# Sheet2-power.net
KiCad netlist of a schematic drawn in Altium Designer
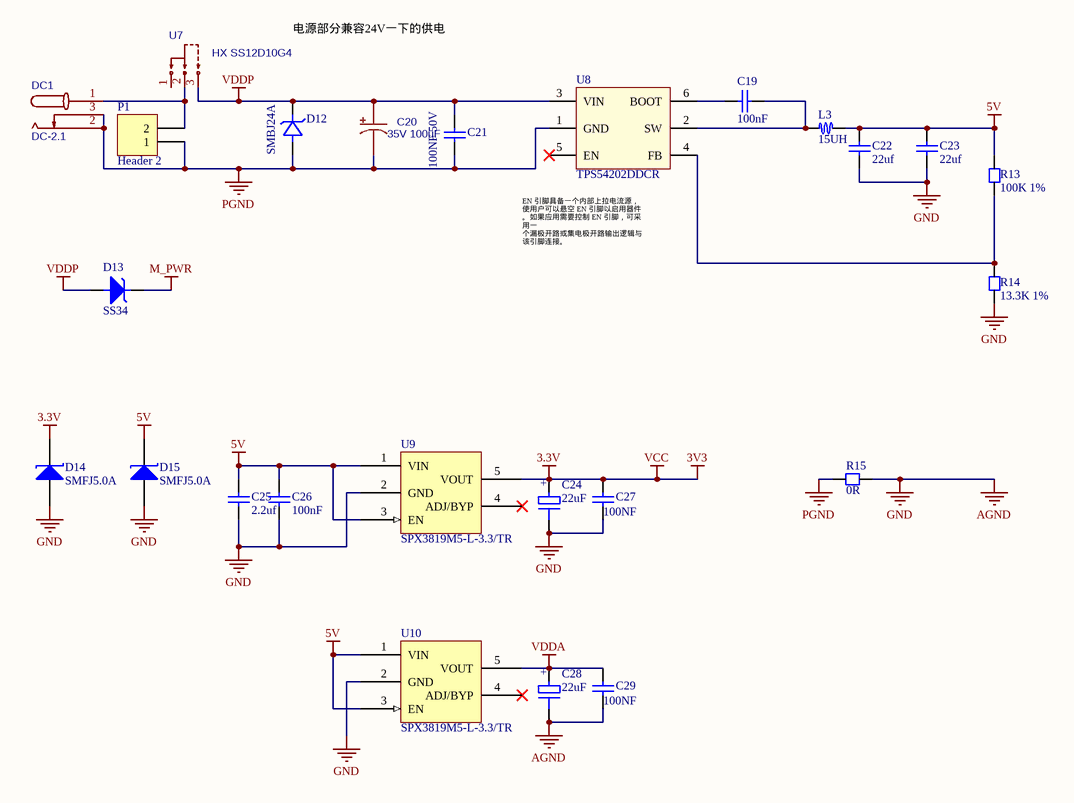
[diagram p0: Sheet2-power.SchDoc]

(export (version "E")
  (design (tool "Eeschema 10.0.6"))
  (components
    (comp (ref "C19")
      (value "100nF")
      (footprint "CC1608-0603")
      (description "0603封装的电容")
      (fields (field (name "PUBLISHER") "Altium Limited"))
      (libsource (lib "base") (part "Cap Chip 0603"))
    )
    (comp (ref "C20")
      (value "35V 100uF")
      (footprint "CAP-SMD_D6.3")
      (description "铝点解电容")
      (fields
        (field (name "BOM_SUPPLIER PART") "C413527")
        (field (name "BOM_MANUFACTURER PART") "EEEFP1C681AP")
        (field (name "CONTRIBUTOR") "LCSC")
      )
      (libsource (lib "base") (part "Cap ECAP SMD"))
    )
    (comp (ref "C21")
      (value "100NF 50V")
      (footprint "CC1608-0603")
      (description "0603封装的电容")
      (fields (field (name "PUBLISHER") "Altium Limited"))
      (libsource (lib "base") (part "Cap Chip 0603"))
    )
    (comp (ref "C22")
      (value "22uf")
      (footprint "CC1608-0603")
      (description "0603封装的电容")
      (fields (field (name "PUBLISHER") "Altium Limited"))
      (libsource (lib "base") (part "Cap Chip 0603"))
    )
    (comp (ref "C23")
      (value "22uf")
      (footprint "CC1608-0603")
      (description "0603封装的电容")
      (fields (field (name "PUBLISHER") "Altium Limited"))
      (libsource (lib "base") (part "Cap Chip 0603"))
    )
    (comp (ref "C24")
      (value "22uF")
      (footprint "TAN-A-1206")
      (description "钽电容")
      (libsource (lib "base") (part "CAP TAN-A-1206"))
    )
    (comp (ref "C25")
      (value "2.2uf")
      (footprint "CC1608-0603")
      (description "0603封装的电容")
      (fields (field (name "PUBLISHER") "Altium Limited"))
      (libsource (lib "base") (part "Cap Chip 0603"))
    )
    (comp (ref "C26")
      (value "100nF")
      (footprint "CC1608-0603")
      (description "0603封装的电容")
      (fields (field (name "PUBLISHER") "Altium Limited"))
      (libsource (lib "base") (part "Cap Chip 0603"))
    )
    (comp (ref "C27")
      (value "100NF")
      (footprint "CC1608-0603")
      (description "贴片电容")
      (libsource (lib "tianxiaohua_Schlib") (part "Chip capacitor"))
    )
    (comp (ref "C28")
      (value "22uF")
      (footprint "TAN-A-1206")
      (description "钽电容")
      (libsource (lib "base") (part "CAP TAN-A-1206"))
    )
    (comp (ref "C29")
      (value "100NF")
      (footprint "CC1608-0603")
      (description "贴片电容")
      (libsource (lib "tianxiaohua_Schlib") (part "Chip capacitor"))
    )
    (comp (ref "D12")
      (value "SMBJ24A")
      (footprint "DO-214 AA")
      (description "TVS稳压二极管")
      (libsource (lib "transistor") (part "SMBJ18A"))
    )
    (comp (ref "D13")
      (value "SS34")
      (footprint "DO-214 AA")
      (description "肖特基二极管")
      (libsource (lib "transistor") (part "SS34"))
    )
    (comp (ref "D14")
      (value "SMFJ5.0A")
      (footprint "SOD-123")
      (description "5V单向贴片TVS瞬变抑制二极管")
      (libsource (lib "transistor") (part "SMFJ5.0A"))
    )
    (comp (ref "D15")
      (value "SMFJ5.0A")
      (footprint "SOD-123")
      (description "5V单向贴片TVS瞬变抑制二极管")
      (libsource (lib "transistor") (part "SMFJ5.0A"))
    )
    (comp (ref "DC1")
      (value "DC-2.1")
      (footprint "DC-IN-SMD_DC-050-25A")
      (description "DC贴片插座")
      (fields
        (field (name "BOM_SUPPLIER PART") "C707275")
        (field (name "BOM_MANUFACTURER PART") "DC-050-25A")
        (field (name "CONTRIBUTOR") "LCSC")
      )
      (libsource (lib "Connectors") (part "DC-050"))
    )
    (comp (ref "L3")
      (value "15UH")
      (footprint "Inductor-0630")
      (description "贴片电感 0630封装")
      (libsource (lib "base") (part "Inductor-0630"))
    )
    (comp (ref "P1")
      (value "Header 2")
      (footprint "HX2.54-2")
      (description "Header, 2-Pin")
      (fields (field (name "PUBLISHER") "Altium Limited"))
      (libsource (lib "Connectors") (part "Header 2"))
    )
    (comp (ref "R13")
      (value "100K 1%")
      (footprint "CR1608-0603")
      (description "0603封装电阻")
      (fields (field (name "PUBLISHER") "Altium Limited"))
      (libsource (lib "") (part "Resistor Chip 0603_1"))
    )
    (comp (ref "R14")
      (value "13.3K 1%")
      (footprint "CR1608-0603")
      (description "0603封装电阻")
      (fields (field (name "PUBLISHER") "Altium Limited"))
      (libsource (lib "") (part "Resistor Chip 0603_1"))
    )
    (comp (ref "R15")
      (value "0R")
      (footprint "CR1608-0603")
      (description "0603封装电阻")
      (fields (field (name "PUBLISHER") "Altium Limited"))
      (libsource (lib "base") (part "Resistor Chip 0603"))
    )
    (comp (ref "U7")
      (value "HX SS12D10G4")
      (footprint "SS12D10-G4")
      (fields (field (name "BOM_SUPPLIER PART") "C5149841") (field (name "CONTRIBUTOR") "lcsc"))
      (libsource (lib "Connectors") (part "SS12D10G4"))
    )
    (comp (ref "U8")
      (value "TPS54202DDCR")
      (footprint "SOT23-6")
      (description "同步降压转换器芯片 500Khz 4.2~28V输入，2A输出")
      (libsource (lib "power-chip") (part "TPS54202DDCR"))
    )
    (comp (ref "U9")
      (value "SPX3819M5-L-3.3/TR")
      (footprint "SOT23-5")
      (description "LDO 3.3V , SOT-23-5 500ma")
      (libsource (lib "power-chip") (part "SPX3819M5-L-3.3/TR"))
    )
    (comp (ref "U10")
      (value "SPX3819M5-L-3.3/TR")
      (footprint "SOT23-5")
      (description "LDO 3.3V , SOT-23-5 500ma")
      (libsource (lib "power-chip") (part "SPX3819M5-L-3.3/TR"))
    )
  )
  (nets
    (net (code "1") (name "3.3V") (class "Default")
      (node (ref "C24") (pin "1") (pinfunction "+_1") (pintype "passive"))
      (node (ref "C27") (pin "1") (pinfunction "1_1") (pintype "passive"))
      (node (ref "D14") (pin "1") (pinfunction "1_1") (pintype "passive"))
      (node (ref "U9") (pin "5") (pinfunction "VOUT_5") (pintype "passive"))
    )
    (net (code "2") (name "5V") (class "Default")
      (node (ref "C22") (pin "2") (pinfunction "2_2") (pintype "passive"))
      (node (ref "C23") (pin "2") (pinfunction "2_2") (pintype "passive"))
      (node (ref "C25") (pin "2") (pinfunction "2_2") (pintype "passive"))
      (node (ref "C26") (pin "2") (pinfunction "2_2") (pintype "passive"))
      (node (ref "D15") (pin "1") (pinfunction "1_1") (pintype "passive"))
      (node (ref "L3") (pin "2") (pinfunction "2_2") (pintype "passive"))
      (node (ref "R13") (pin "2") (pinfunction "2_2") (pintype "passive"))
      (node (ref "U10") (pin "1") (pinfunction "VIN_1") (pintype "power_in"))
      (node (ref "U10") (pin "3") (pinfunction "EN_3") (pintype "input"))
      (node (ref "U9") (pin "1") (pinfunction "VIN_1") (pintype "power_in"))
      (node (ref "U9") (pin "3") (pinfunction "EN_3") (pintype "input"))
    )
    (net (code "3") (name "AGND") (class "Default")
      (node (ref "C22") (pin "1") (pinfunction "1_1") (pintype "passive"))
      (node (ref "C23") (pin "1") (pinfunction "1_1") (pintype "passive"))
      (node (ref "C24") (pin "2") (pinfunction "-_2") (pintype "passive"))
      (node (ref "C25") (pin "1") (pinfunction "1_1") (pintype "passive"))
      (node (ref "C26") (pin "1") (pinfunction "1_1") (pintype "passive"))
      (node (ref "C27") (pin "2") (pinfunction "2_2") (pintype "passive"))
      (node (ref "C28") (pin "2") (pinfunction "-_2") (pintype "passive"))
      (node (ref "C29") (pin "2") (pinfunction "2_2") (pintype "passive"))
      (node (ref "D14") (pin "2") (pinfunction "2_2") (pintype "passive"))
      (node (ref "D15") (pin "2") (pinfunction "2_2") (pintype "passive"))
      (node (ref "R14") (pin "1") (pinfunction "1_1") (pintype "passive"))
      (node (ref "R15") (pin "1") (pinfunction "1_1") (pintype "passive"))
      (node (ref "U10") (pin "2") (pinfunction "GND_2") (pintype "power_in"))
      (node (ref "U9") (pin "2") (pinfunction "GND_2") (pintype "power_in"))
    )
    (net (code "4") (name "M_PWR") (class "Default")
      (node (ref "D13") (pin "1") (pinfunction "K_1") (pintype "passive"))
    )
    (net (code "5") (name "Net-(DC1-Pad1)") (class "Default")
      (node (ref "DC1") (pin "1") (pinfunction "1_1") (pintype "passive"))
      (node (ref "P1") (pin "2") (pinfunction "2_2") (pintype "passive"))
      (node (ref "U7") (pin "2") (pinfunction "2_2") (pintype "passive"))
    )
    (net (code "6") (name "Net-(U8-BOOT)") (class "Default")
      (node (ref "C19") (pin "1") (pinfunction "1_1") (pintype "passive"))
      (node (ref "U8") (pin "6") (pinfunction "BOOT_6") (pintype "passive"))
    )
    (net (code "7") (name "Net-(U8-FB)") (class "Default")
      (node (ref "R13") (pin "1") (pinfunction "1_1") (pintype "passive"))
      (node (ref "R14") (pin "2") (pinfunction "2_2") (pintype "passive"))
      (node (ref "U8") (pin "4") (pinfunction "FB_4") (pintype "passive"))
    )
    (net (code "8") (name "Net-(U8-SW)") (class "Default")
      (node (ref "C19") (pin "2") (pinfunction "2_2") (pintype "passive"))
      (node (ref "L3") (pin "1") (pinfunction "1_1") (pintype "passive"))
      (node (ref "U8") (pin "2") (pinfunction "SW_2") (pintype "passive"))
    )
    (net (code "9") (name "PGND") (class "Default")
      (node (ref "C20") (pin "2") (pinfunction "2_2") (pintype "passive"))
      (node (ref "C21") (pin "1") (pinfunction "1_1") (pintype "passive"))
      (node (ref "D12") (pin "2") (pinfunction "A_2") (pintype "passive"))
      (node (ref "DC1") (pin "2") (pinfunction "2_2") (pintype "passive"))
      (node (ref "DC1") (pin "3") (pinfunction "3_3") (pintype "passive"))
      (node (ref "P1") (pin "1") (pinfunction "1_1") (pintype "passive"))
      (node (ref "R15") (pin "2") (pinfunction "2_2") (pintype "passive"))
      (node (ref "U8") (pin "1") (pinfunction "GND_1") (pintype "passive"))
    )
    (net (code "10") (name "VDDA") (class "Default")
      (node (ref "C28") (pin "1") (pinfunction "+_1") (pintype "passive"))
      (node (ref "C29") (pin "1") (pinfunction "1_1") (pintype "passive"))
      (node (ref "U10") (pin "5") (pinfunction "VOUT_5") (pintype "passive"))
    )
    (net (code "11") (name "VDDP") (class "Default")
      (node (ref "C20") (pin "1") (pinfunction "1_1") (pintype "passive"))
      (node (ref "C21") (pin "2") (pinfunction "2_2") (pintype "passive"))
      (node (ref "D12") (pin "1") (pinfunction "K_1") (pintype "passive"))
      (node (ref "D13") (pin "2") (pinfunction "A_2") (pintype "passive"))
      (node (ref "U7") (pin "3") (pinfunction "3_3") (pintype "passive"))
      (node (ref "U8") (pin "3") (pinfunction "VIN_3") (pintype "passive"))
    )
    (net (code "12") (name "unconnected-(U7-Pad1)") (class "Default")
      (node (ref "U7") (pin "1") (pinfunction "1_1") (pintype "passive"))
    )
    (net (code "13") (name "unconnected-(U8-EN-Pad5)") (class "Default")
      (node (ref "U8") (pin "5") (pinfunction "EN_5") (pintype "passive+no_connect"))
    )
    (net (code "14") (name "unconnected-(U9-ADJ{slash}BYP-Pad4)") (class "Default")
      (node (ref "U9") (pin "4") (pinfunction "ADJ/BYP_4") (pintype "passive+no_connect"))
    )
    (net (code "15") (name "unconnected-(U10-ADJ{slash}BYP-Pad4)") (class "Default")
      (node (ref "U10") (pin "4") (pinfunction "ADJ/BYP_4") (pintype "passive+no_connect"))
    )
  )
)
